# Sheet1.net
KiCad netlist of a schematic drawn in Altium Designer
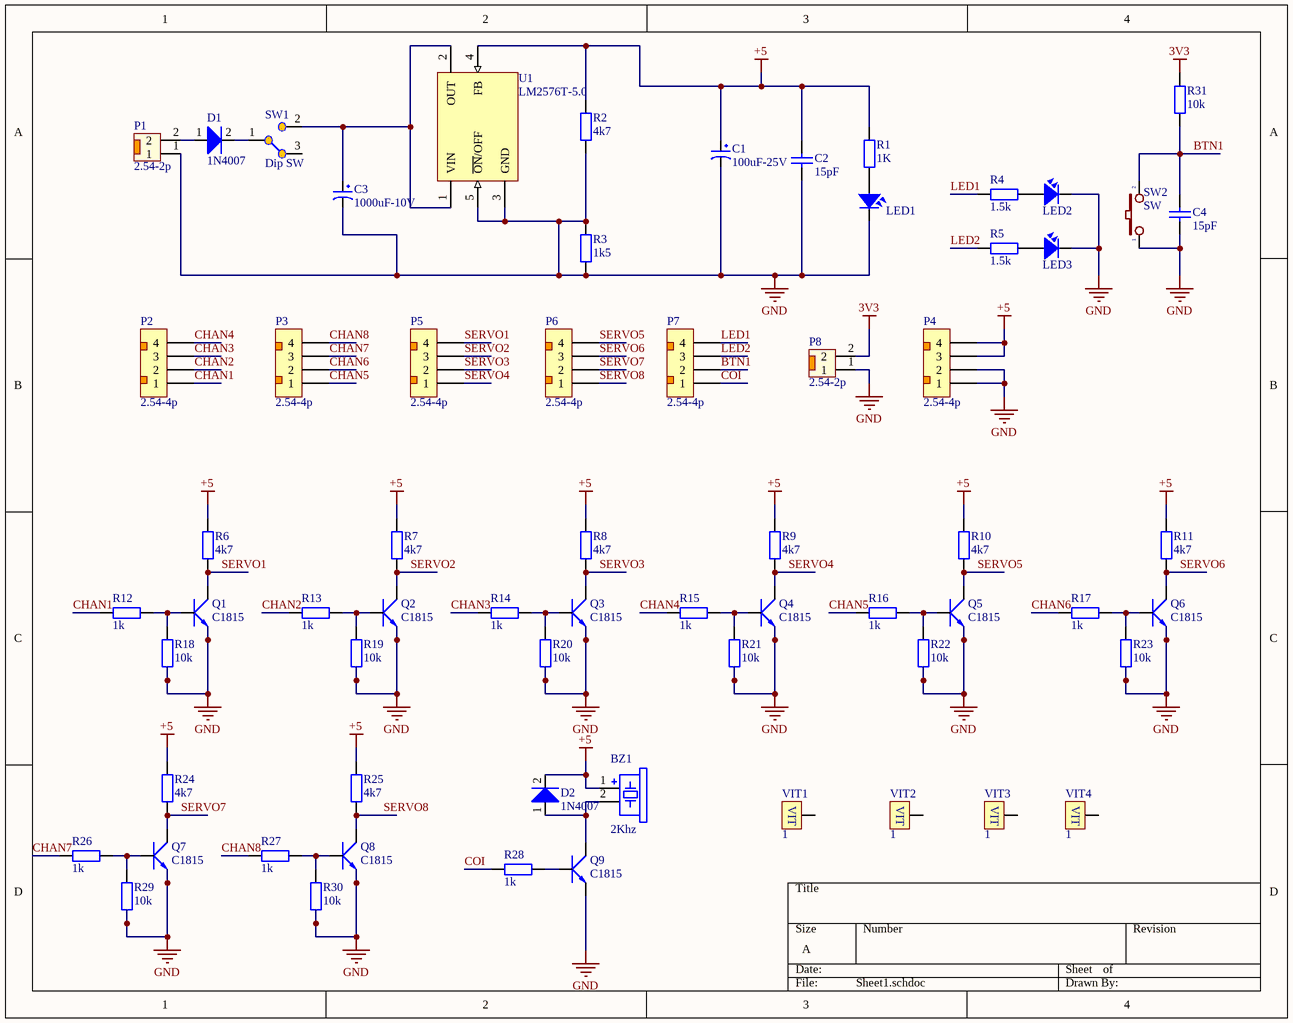
[diagram p0: Sheet1.schdoc]

(export (version "E")
  (design (tool "Eeschema 10.0.6"))
  (components
    (comp (ref "BZ1")
      (value "2Khz")
      (footprint "coi xung")
      (description "Cắm")
      (libsource (lib "NhomLib (1)") (part "Coi xung 2Khz"))
    )
    (comp (ref "C1")
      (value "100uF-25V")
      (footprint "tu hoa 5mm")
      (description "Cắm")
      (libsource (lib "NhomLib (1)") (part "Tu Hoa 100uF 25V 6x11"))
    )
    (comp (ref "C2")
      (value "15pF")
      (footprint "tu gom")
      (description "Cắm")
      (libsource (lib "NhomLib (1)") (part "Tu gom 15pF 50V"))
    )
    (comp (ref "C3")
      (value "1000uF-10V")
      (footprint "tu hoa 10mm")
      (description "Cắm")
      (libsource (lib "NhomLib (1)") (part "Tu Hoa 1000uF 10V 10x12"))
    )
    (comp (ref "C4")
      (value "15pF")
      (footprint "tu gom")
      (description "Cắm")
      (libsource (lib "NhomLib (1)") (part "Tu gom 15pF 50V"))
    )
    (comp (ref "D1")
      (value "1N4007")
      (footprint "1N4007")
      (description "Diode LS 1A 1000V DO-41")
      (libsource (lib "NhomLib (1)") (part "1N4007"))
    )
    (comp (ref "D2")
      (value "1N4007")
      (footprint "1N4007")
      (description "Diode LS 1A 1000V DO-41")
      (libsource (lib "NhomLib (1)") (part "1N4007"))
    )
    (comp (ref "LED1")
      (value "LED")
      (footprint "LED-3")
      (description "LED Single colour Green and Red")
      (libsource (lib "NhomLib (1)") (part "LED"))
    )
    (comp (ref "LED2")
      (value "LED")
      (footprint "LED-3")
      (description "LED Single colour Green and Red")
      (libsource (lib "NhomLib (1)") (part "LED"))
    )
    (comp (ref "LED3")
      (value "LED")
      (footprint "LED-3")
      (description "LED Single colour Green and Red")
      (libsource (lib "NhomLib (1)") (part "LED"))
    )
    (comp (ref "P1")
      (value "2.54-2p")
      (footprint "Header Duc Thang 2P 2.54")
      (description "Cắm")
      (libsource (lib "NhomLib (1)") (part "Header 2.54-2p Duc Thang"))
    )
    (comp (ref "P2")
      (value "2.54-4p")
      (footprint "Header Duc Thang 4p 2.54")
      (description "Cắm")
      (libsource (lib "NhomLib (1)") (part "Header 2.54_4p Duc Thang"))
    )
    (comp (ref "P3")
      (value "2.54-4p")
      (footprint "Header Duc Thang 4p 2.54")
      (description "Cắm")
      (libsource (lib "NhomLib (1)") (part "Header 2.54_4p Duc Thang"))
    )
    (comp (ref "P4")
      (value "2.54-4p")
      (footprint "Header Duc Thang 4p 2.54")
      (description "Cắm")
      (libsource (lib "NhomLib (1)") (part "Header 2.54_4p Duc Thang"))
    )
    (comp (ref "P5")
      (value "2.54-4p")
      (footprint "Header Duc Thang 4p 2.54")
      (description "Cắm")
      (libsource (lib "NhomLib (1)") (part "Header 2.54_4p Duc Thang"))
    )
    (comp (ref "P6")
      (value "2.54-4p")
      (footprint "Header Duc Thang 4p 2.54")
      (description "Cắm")
      (libsource (lib "NhomLib (1)") (part "Header 2.54_4p Duc Thang"))
    )
    (comp (ref "P7")
      (value "2.54-4p")
      (footprint "Header Duc Thang 4p 2.54")
      (description "Cắm")
      (libsource (lib "NhomLib (1)") (part "Header 2.54_4p Duc Thang"))
    )
    (comp (ref "P8")
      (value "2.54-2p")
      (footprint "Header Duc Thang 2P 2.54")
      (description "Cắm")
      (libsource (lib "NhomLib (1)") (part "Header 2.54-2p Duc Thang"))
    )
    (comp (ref "Q1")
      (value "C1815")
      (footprint "QTO-92")
      (description "NPN 600mW, ECB")
      (libsource (lib "syhaunguyen") (part "C1815"))
    )
    (comp (ref "Q2")
      (value "C1815")
      (footprint "QTO-92")
      (description "NPN 600mW, ECB")
      (libsource (lib "syhaunguyen") (part "C1815"))
    )
    (comp (ref "Q3")
      (value "C1815")
      (footprint "QTO-92")
      (description "NPN 600mW, ECB")
      (libsource (lib "syhaunguyen") (part "C1815"))
    )
    (comp (ref "Q4")
      (value "C1815")
      (footprint "QTO-92")
      (description "NPN 600mW, ECB")
      (libsource (lib "syhaunguyen") (part "C1815"))
    )
    (comp (ref "Q5")
      (value "C1815")
      (footprint "QTO-92")
      (description "NPN 600mW, ECB")
      (libsource (lib "syhaunguyen") (part "C1815"))
    )
    (comp (ref "Q6")
      (value "C1815")
      (footprint "QTO-92")
      (description "NPN 600mW, ECB")
      (libsource (lib "syhaunguyen") (part "C1815"))
    )
    (comp (ref "Q7")
      (value "C1815")
      (footprint "QTO-92")
      (description "NPN 600mW, ECB")
      (libsource (lib "syhaunguyen") (part "C1815"))
    )
    (comp (ref "Q8")
      (value "C1815")
      (footprint "QTO-92")
      (description "NPN 600mW, ECB")
      (libsource (lib "syhaunguyen") (part "C1815"))
    )
    (comp (ref "Q9")
      (value "C1815")
      (footprint "QTO-92")
      (description "NPN 600mW, ECB")
      (libsource (lib "syhaunguyen") (part "C1815"))
    )
    (comp (ref "R1")
      (value "1K")
      (footprint "tro vach 1/4w")
      (description "Cắm")
      (libsource (lib "NhomLib (1)") (part "Tro Vach 1/4W 5% 1.5k"))
    )
    (comp (ref "R2")
      (value "4k7")
      (footprint "tro vach 1/4w")
      (description "Cắm")
      (libsource (lib "NhomLib (1)") (part "Tro Vach 1/4W 5% 1.5k"))
    )
    (comp (ref "R3")
      (value "1k5")
      (footprint "tro vach 1/4w")
      (description "Cắm")
      (libsource (lib "NhomLib (1)") (part "Tro Vach 1/4W 5% 1.5k"))
    )
    (comp (ref "R4")
      (value "1.5k")
      (footprint "tro vach 1/4w")
      (description "Cắm")
      (libsource (lib "NhomLib (1)") (part "Tro Vach 1/4W 5% 1.5k"))
    )
    (comp (ref "R5")
      (value "1.5k")
      (footprint "tro vach 1/4w")
      (description "Cắm")
      (libsource (lib "NhomLib (1)") (part "Tro Vach 1/4W 5% 1.5k"))
    )
    (comp (ref "R6")
      (value "4k7")
      (footprint "tro vach 1/4w")
      (description "Cắm")
      (libsource (lib "NhomLib (1)") (part "Tro Vach 1/4W 5% 1.5k"))
    )
    (comp (ref "R7")
      (value "4k7")
      (footprint "tro vach 1/4w")
      (description "Cắm")
      (libsource (lib "NhomLib (1)") (part "Tro Vach 1/4W 5% 1.5k"))
    )
    (comp (ref "R8")
      (value "4k7")
      (footprint "tro vach 1/4w")
      (description "Cắm")
      (libsource (lib "NhomLib (1)") (part "Tro Vach 1/4W 5% 1.5k"))
    )
    (comp (ref "R9")
      (value "4k7")
      (footprint "tro vach 1/4w")
      (description "Cắm")
      (libsource (lib "NhomLib (1)") (part "Tro Vach 1/4W 5% 1.5k"))
    )
    (comp (ref "R10")
      (value "4k7")
      (footprint "tro vach 1/4w")
      (description "Cắm")
      (libsource (lib "NhomLib (1)") (part "Tro Vach 1/4W 5% 1.5k"))
    )
    (comp (ref "R11")
      (value "4k7")
      (footprint "tro vach 1/4w")
      (description "Cắm")
      (libsource (lib "NhomLib (1)") (part "Tro Vach 1/4W 5% 1.5k"))
    )
    (comp (ref "R12")
      (value "1k")
      (footprint "tro vach 1/4w")
      (description "Cắm")
      (libsource (lib "NhomLib (1)") (part "Tro Vach 1/4W 5% 1.5k"))
    )
    (comp (ref "R13")
      (value "1k")
      (footprint "tro vach 1/4w")
      (description "Cắm")
      (libsource (lib "NhomLib (1)") (part "Tro Vach 1/4W 5% 1.5k"))
    )
    (comp (ref "R14")
      (value "1k")
      (footprint "tro vach 1/4w")
      (description "Cắm")
      (libsource (lib "NhomLib (1)") (part "Tro Vach 1/4W 5% 1.5k"))
    )
    (comp (ref "R15")
      (value "1k")
      (footprint "tro vach 1/4w")
      (description "Cắm")
      (libsource (lib "NhomLib (1)") (part "Tro Vach 1/4W 5% 1.5k"))
    )
    (comp (ref "R16")
      (value "1k")
      (footprint "tro vach 1/4w")
      (description "Cắm")
      (libsource (lib "NhomLib (1)") (part "Tro Vach 1/4W 5% 1.5k"))
    )
    (comp (ref "R17")
      (value "1k")
      (footprint "tro vach 1/4w")
      (description "Cắm")
      (libsource (lib "NhomLib (1)") (part "Tro Vach 1/4W 5% 1.5k"))
    )
    (comp (ref "R18")
      (value "10k")
      (footprint "tro vach 1/4w")
      (description "Cắm")
      (libsource (lib "NhomLib (1)") (part "Tro Vach 1/4W 5% 1.5k"))
    )
    (comp (ref "R19")
      (value "10k")
      (footprint "tro vach 1/4w")
      (description "Cắm")
      (libsource (lib "NhomLib (1)") (part "Tro Vach 1/4W 5% 1.5k"))
    )
    (comp (ref "R20")
      (value "10k")
      (footprint "tro vach 1/4w")
      (description "Cắm")
      (libsource (lib "NhomLib (1)") (part "Tro Vach 1/4W 5% 1.5k"))
    )
    (comp (ref "R21")
      (value "10k")
      (footprint "tro vach 1/4w")
      (description "Cắm")
      (libsource (lib "NhomLib (1)") (part "Tro Vach 1/4W 5% 1.5k"))
    )
    (comp (ref "R22")
      (value "10k")
      (footprint "tro vach 1/4w")
      (description "Cắm")
      (libsource (lib "NhomLib (1)") (part "Tro Vach 1/4W 5% 1.5k"))
    )
    (comp (ref "R23")
      (value "10k")
      (footprint "tro vach 1/4w")
      (description "Cắm")
      (libsource (lib "NhomLib (1)") (part "Tro Vach 1/4W 5% 1.5k"))
    )
    (comp (ref "R24")
      (value "4k7")
      (footprint "tro vach 1/4w")
      (description "Cắm")
      (libsource (lib "NhomLib (1)") (part "Tro Vach 1/4W 5% 1.5k"))
    )
    (comp (ref "R25")
      (value "4k7")
      (footprint "tro vach 1/4w")
      (description "Cắm")
      (libsource (lib "NhomLib (1)") (part "Tro Vach 1/4W 5% 1.5k"))
    )
    (comp (ref "R26")
      (value "1k")
      (footprint "tro vach 1/4w")
      (description "Cắm")
      (libsource (lib "NhomLib (1)") (part "Tro Vach 1/4W 5% 1.5k"))
    )
    (comp (ref "R27")
      (value "1k")
      (footprint "tro vach 1/4w")
      (description "Cắm")
      (libsource (lib "NhomLib (1)") (part "Tro Vach 1/4W 5% 1.5k"))
    )
    (comp (ref "R28")
      (value "1k")
      (footprint "tro vach 1/4w")
      (description "Cắm")
      (libsource (lib "NhomLib (1)") (part "Tro Vach 1/4W 5% 1.5k"))
    )
    (comp (ref "R29")
      (value "10k")
      (footprint "tro vach 1/4w")
      (description "Cắm")
      (libsource (lib "NhomLib (1)") (part "Tro Vach 1/4W 5% 1.5k"))
    )
    (comp (ref "R30")
      (value "10k")
      (footprint "tro vach 1/4w")
      (description "Cắm")
      (libsource (lib "NhomLib (1)") (part "Tro Vach 1/4W 5% 1.5k"))
    )
    (comp (ref "R31")
      (value "10k")
      (footprint "tro vach 1/4w")
      (description "Cắm")
      (libsource (lib "NhomLib (1)") (part "Tro Vach 1/4W 5% 1.5k"))
    )
    (comp (ref "SW1")
      (value "Dip SW")
      (footprint "SW3P")
      (description "Dip Switch 3 pin")
      (libsource (lib "VPMyLibrary") (part "Switch3P"))
    )
    (comp (ref "SW2")
      (value "SW")
      (footprint "SW2")
      (description "Switch button 2 pin")
      (libsource (lib "syhaunguyen") (part "SW2"))
    )
    (comp (ref "U1")
      (value "LM2576T-5.0")
      (footprint "LM2576t")
      (description "SIMPLE SWITCHER; 3A Step-Down Voltage Regulator")
      (fields
        (field (name "MANUFACTURER") "National Semiconductor")
        (field (name "DIGIKEYPARTNUMBER") "LM2576T-5.0-ND")
        (field (name "PUBLISHER") "Altium Limited")
      )
      (libsource (lib "NBBLib 14-03-2012") (part "LM2576T-5.0"))
    )
    (comp (ref "VIT1")
      (value "1")
      (footprint "VIT")
      (description "Oc Vit")
      (libsource (lib "NhomLib (1)") (part "VIT"))
    )
    (comp (ref "VIT2")
      (value "1")
      (footprint "VIT")
      (description "Oc Vit")
      (libsource (lib "NhomLib (1)") (part "VIT"))
    )
    (comp (ref "VIT3")
      (value "1")
      (footprint "VIT")
      (description "Oc Vit")
      (libsource (lib "NhomLib (1)") (part "VIT"))
    )
    (comp (ref "VIT4")
      (value "1")
      (footprint "VIT")
      (description "Oc Vit")
      (libsource (lib "NhomLib (1)") (part "VIT"))
    )
  )
  (nets
    (net (code "1") (name "+5") (class "Default")
      (node (ref "BZ1") (pin "1") (pinfunction "1_1") (pintype "passive"))
      (node (ref "C1") (pin "1") (pinfunction "1_1") (pintype "passive"))
      (node (ref "C2") (pin "1") (pinfunction "1_1") (pintype "passive"))
      (node (ref "D2") (pin "2") (pinfunction "K_2") (pintype "passive"))
      (node (ref "P4") (pin "3") (pinfunction "3_3") (pintype "passive"))
      (node (ref "P4") (pin "4") (pinfunction "4_4") (pintype "passive"))
      (node (ref "R1") (pin "2") (pinfunction "2_2") (pintype "passive"))
      (node (ref "R10") (pin "2") (pinfunction "2_2") (pintype "passive"))
      (node (ref "R11") (pin "2") (pinfunction "2_2") (pintype "passive"))
      (node (ref "R2") (pin "2") (pinfunction "2_2") (pintype "passive"))
      (node (ref "R24") (pin "2") (pinfunction "2_2") (pintype "passive"))
      (node (ref "R25") (pin "2") (pinfunction "2_2") (pintype "passive"))
      (node (ref "R6") (pin "2") (pinfunction "2_2") (pintype "passive"))
      (node (ref "R7") (pin "2") (pinfunction "2_2") (pintype "passive"))
      (node (ref "R8") (pin "2") (pinfunction "2_2") (pintype "passive"))
      (node (ref "R9") (pin "2") (pinfunction "2_2") (pintype "passive"))
      (node (ref "U1") (pin "4") (pinfunction "FB_4") (pintype "input"))
    )
    (net (code "2") (name "/BTN1") (class "Default")
      (node (ref "C4") (pin "1") (pinfunction "1_1") (pintype "passive"))
      (node (ref "P7") (pin "2") (pinfunction "2_2") (pintype "passive"))
      (node (ref "R31") (pin "1") (pinfunction "1_1") (pintype "passive"))
      (node (ref "SW2") (pin "2") (pinfunction "2_2") (pintype "passive"))
    )
    (net (code "3") (name "/CHAN1") (class "Default")
      (node (ref "P2") (pin "1") (pinfunction "1_1") (pintype "passive"))
      (node (ref "R12") (pin "1") (pinfunction "1_1") (pintype "passive"))
    )
    (net (code "4") (name "/CHAN2") (class "Default")
      (node (ref "P2") (pin "2") (pinfunction "2_2") (pintype "passive"))
      (node (ref "R13") (pin "1") (pinfunction "1_1") (pintype "passive"))
    )
    (net (code "5") (name "/CHAN3") (class "Default")
      (node (ref "P2") (pin "3") (pinfunction "3_3") (pintype "passive"))
      (node (ref "R14") (pin "1") (pinfunction "1_1") (pintype "passive"))
    )
    (net (code "6") (name "/CHAN4") (class "Default")
      (node (ref "P2") (pin "4") (pinfunction "4_4") (pintype "passive"))
      (node (ref "R15") (pin "1") (pinfunction "1_1") (pintype "passive"))
    )
    (net (code "7") (name "/CHAN5") (class "Default")
      (node (ref "P3") (pin "1") (pinfunction "1_1") (pintype "passive"))
      (node (ref "R16") (pin "1") (pinfunction "1_1") (pintype "passive"))
    )
    (net (code "8") (name "/CHAN6") (class "Default")
      (node (ref "P3") (pin "2") (pinfunction "2_2") (pintype "passive"))
      (node (ref "R17") (pin "1") (pinfunction "1_1") (pintype "passive"))
    )
    (net (code "9") (name "/CHAN7") (class "Default")
      (node (ref "P3") (pin "3") (pinfunction "3_3") (pintype "passive"))
      (node (ref "R26") (pin "1") (pinfunction "1_1") (pintype "passive"))
    )
    (net (code "10") (name "/CHAN8") (class "Default")
      (node (ref "P3") (pin "4") (pinfunction "4_4") (pintype "passive"))
      (node (ref "R27") (pin "1") (pinfunction "1_1") (pintype "passive"))
    )
    (net (code "11") (name "/COI") (class "Default")
      (node (ref "P7") (pin "1") (pinfunction "1_1") (pintype "passive"))
      (node (ref "R28") (pin "1") (pinfunction "1_1") (pintype "passive"))
    )
    (net (code "12") (name "/LED1") (class "Default")
      (node (ref "P7") (pin "4") (pinfunction "4_4") (pintype "passive"))
      (node (ref "R4") (pin "2") (pinfunction "2_2") (pintype "passive"))
    )
    (net (code "13") (name "/LED2") (class "Default")
      (node (ref "P7") (pin "3") (pinfunction "3_3") (pintype "passive"))
      (node (ref "R5") (pin "2") (pinfunction "2_2") (pintype "passive"))
    )
    (net (code "14") (name "/SERVO1") (class "Default")
      (node (ref "P5") (pin "4") (pinfunction "4_4") (pintype "passive"))
      (node (ref "Q1") (pin "2") (pinfunction "C_2") (pintype "passive"))
      (node (ref "R6") (pin "1") (pinfunction "1_1") (pintype "passive"))
    )
    (net (code "15") (name "/SERVO2") (class "Default")
      (node (ref "P5") (pin "3") (pinfunction "3_3") (pintype "passive"))
      (node (ref "Q2") (pin "2") (pinfunction "C_2") (pintype "passive"))
      (node (ref "R7") (pin "1") (pinfunction "1_1") (pintype "passive"))
    )
    (net (code "16") (name "/SERVO3") (class "Default")
      (node (ref "P5") (pin "2") (pinfunction "2_2") (pintype "passive"))
      (node (ref "Q3") (pin "2") (pinfunction "C_2") (pintype "passive"))
      (node (ref "R8") (pin "1") (pinfunction "1_1") (pintype "passive"))
    )
    (net (code "17") (name "/SERVO4") (class "Default")
      (node (ref "P5") (pin "1") (pinfunction "1_1") (pintype "passive"))
      (node (ref "Q4") (pin "2") (pinfunction "C_2") (pintype "passive"))
      (node (ref "R9") (pin "1") (pinfunction "1_1") (pintype "passive"))
    )
    (net (code "18") (name "/SERVO5") (class "Default")
      (node (ref "P6") (pin "4") (pinfunction "4_4") (pintype "passive"))
      (node (ref "Q5") (pin "2") (pinfunction "C_2") (pintype "passive"))
      (node (ref "R10") (pin "1") (pinfunction "1_1") (pintype "passive"))
    )
    (net (code "19") (name "/SERVO6") (class "Default")
      (node (ref "P6") (pin "3") (pinfunction "3_3") (pintype "passive"))
      (node (ref "Q6") (pin "2") (pinfunction "C_2") (pintype "passive"))
      (node (ref "R11") (pin "1") (pinfunction "1_1") (pintype "passive"))
    )
    (net (code "20") (name "/SERVO7") (class "Default")
      (node (ref "P6") (pin "2") (pinfunction "2_2") (pintype "passive"))
      (node (ref "Q7") (pin "2") (pinfunction "C_2") (pintype "passive"))
      (node (ref "R24") (pin "1") (pinfunction "1_1") (pintype "passive"))
    )
    (net (code "21") (name "/SERVO8") (class "Default")
      (node (ref "P6") (pin "1") (pinfunction "1_1") (pintype "passive"))
      (node (ref "Q8") (pin "2") (pinfunction "C_2") (pintype "passive"))
      (node (ref "R25") (pin "1") (pinfunction "1_1") (pintype "passive"))
    )
    (net (code "22") (name "3V3") (class "Default")
      (node (ref "P8") (pin "2") (pinfunction "2_2") (pintype "passive"))
      (node (ref "R31") (pin "2") (pinfunction "2_2") (pintype "passive"))
    )
    (net (code "23") (name "GND") (class "Default")
      (node (ref "C1") (pin "2") (pinfunction "2_2") (pintype "passive"))
      (node (ref "C2") (pin "2") (pinfunction "2_2") (pintype "passive"))
      (node (ref "C3") (pin "2") (pinfunction "2_2") (pintype "passive"))
      (node (ref "C4") (pin "2") (pinfunction "2_2") (pintype "passive"))
      (node (ref "LED1") (pin "2") (pinfunction "2_2") (pintype "passive"))
      (node (ref "LED2") (pin "2") (pinfunction "2_2") (pintype "passive"))
      (node (ref "LED3") (pin "2") (pinfunction "2_2") (pintype "passive"))
      (node (ref "P1") (pin "1") (pinfunction "1_1") (pintype "passive"))
      (node (ref "P4") (pin "1") (pinfunction "1_1") (pintype "passive"))
      (node (ref "P4") (pin "2") (pinfunction "2_2") (pintype "passive"))
      (node (ref "P8") (pin "1") (pinfunction "1_1") (pintype "passive"))
      (node (ref "Q1") (pin "1") (pinfunction "E_1") (pintype "passive"))
      (node (ref "Q2") (pin "1") (pinfunction "E_1") (pintype "passive"))
      (node (ref "Q3") (pin "1") (pinfunction "E_1") (pintype "passive"))
      (node (ref "Q4") (pin "1") (pinfunction "E_1") (pintype "passive"))
      (node (ref "Q5") (pin "1") (pinfunction "E_1") (pintype "passive"))
      (node (ref "Q6") (pin "1") (pinfunction "E_1") (pintype "passive"))
      (node (ref "Q7") (pin "1") (pinfunction "E_1") (pintype "passive"))
      (node (ref "Q8") (pin "1") (pinfunction "E_1") (pintype "passive"))
      (node (ref "Q9") (pin "1") (pinfunction "E_1") (pintype "passive"))
      (node (ref "R18") (pin "1") (pinfunction "1_1") (pintype "passive"))
      (node (ref "R19") (pin "1") (pinfunction "1_1") (pintype "passive"))
      (node (ref "R2") (pin "1") (pinfunction "1_1") (pintype "passive"))
      (node (ref "R20") (pin "1") (pinfunction "1_1") (pintype "passive"))
      (node (ref "R21") (pin "1") (pinfunction "1_1") (pintype "passive"))
      (node (ref "R22") (pin "1") (pinfunction "1_1") (pintype "passive"))
      (node (ref "R23") (pin "1") (pinfunction "1_1") (pintype "passive"))
      (node (ref "R29") (pin "1") (pinfunction "1_1") (pintype "passive"))
      (node (ref "R3") (pin "1") (pinfunction "1_1") (pintype "passive"))
      (node (ref "R3") (pin "2") (pinfunction "2_2") (pintype "passive"))
      (node (ref "R30") (pin "1") (pinfunction "1_1") (pintype "passive"))
      (node (ref "SW2") (pin "1") (pinfunction "1_1") (pintype "passive"))
      (node (ref "U1") (pin "3") (pinfunction "GND_3") (pintype "power_in"))
      (node (ref "U1") (pin "5") (pinfunction "~{ON}/OFF_5") (pintype "input"))
    )
    (net (code "24") (name "Net-(D1-A)") (class "Default")
      (node (ref "D1") (pin "1") (pinfunction "A_1") (pintype "passive"))
      (node (ref "P1") (pin "2") (pinfunction "2_2") (pintype "passive"))
    )
    (net (code "25") (name "Net-(D1-K)") (class "Default")
      (node (ref "D1") (pin "2") (pinfunction "K_2") (pintype "passive"))
      (node (ref "SW1") (pin "1") (pinfunction "COM_1") (pintype "passive"))
    )
    (net (code "26") (name "Net-(D2-A)") (class "Default")
      (node (ref "BZ1") (pin "2") (pinfunction "2_2") (pintype "passive"))
      (node (ref "D2") (pin "1") (pinfunction "A_1") (pintype "passive"))
      (node (ref "Q9") (pin "2") (pinfunction "C_2") (pintype "passive"))
    )
    (net (code "27") (name "Net-(LED1-Pad1)") (class "Default")
      (node (ref "LED1") (pin "1") (pinfunction "1_1") (pintype "passive"))
      (node (ref "R1") (pin "1") (pinfunction "1_1") (pintype "passive"))
    )
    (net (code "28") (name "Net-(LED2-Pad1)") (class "Default")
      (node (ref "LED2") (pin "1") (pinfunction "1_1") (pintype "passive"))
      (node (ref "R4") (pin "1") (pinfunction "1_1") (pintype "passive"))
    )
    (net (code "29") (name "Net-(LED3-Pad1)") (class "Default")
      (node (ref "LED3") (pin "1") (pinfunction "1_1") (pintype "passive"))
      (node (ref "R5") (pin "1") (pinfunction "1_1") (pintype "passive"))
    )
    (net (code "30") (name "Net-(Q1-B)") (class "Default")
      (node (ref "Q1") (pin "3") (pinfunction "B_3") (pintype "passive"))
      (node (ref "R12") (pin "2") (pinfunction "2_2") (pintype "passive"))
      (node (ref "R18") (pin "2") (pinfunction "2_2") (pintype "passive"))
    )
    (net (code "31") (name "Net-(Q2-B)") (class "Default")
      (node (ref "Q2") (pin "3") (pinfunction "B_3") (pintype "passive"))
      (node (ref "R13") (pin "2") (pinfunction "2_2") (pintype "passive"))
      (node (ref "R19") (pin "2") (pinfunction "2_2") (pintype "passive"))
    )
    (net (code "32") (name "Net-(Q3-B)") (class "Default")
      (node (ref "Q3") (pin "3") (pinfunction "B_3") (pintype "passive"))
      (node (ref "R14") (pin "2") (pinfunction "2_2") (pintype "passive"))
      (node (ref "R20") (pin "2") (pinfunction "2_2") (pintype "passive"))
    )
    (net (code "33") (name "Net-(Q4-B)") (class "Default")
      (node (ref "Q4") (pin "3") (pinfunction "B_3") (pintype "passive"))
      (node (ref "R15") (pin "2") (pinfunction "2_2") (pintype "passive"))
      (node (ref "R21") (pin "2") (pinfunction "2_2") (pintype "passive"))
    )
    (net (code "34") (name "Net-(Q5-B)") (class "Default")
      (node (ref "Q5") (pin "3") (pinfunction "B_3") (pintype "passive"))
      (node (ref "R16") (pin "2") (pinfunction "2_2") (pintype "passive"))
      (node (ref "R22") (pin "2") (pinfunction "2_2") (pintype "passive"))
    )
    (net (code "35") (name "Net-(Q6-B)") (class "Default")
      (node (ref "Q6") (pin "3") (pinfunction "B_3") (pintype "passive"))
      (node (ref "R17") (pin "2") (pinfunction "2_2") (pintype "passive"))
      (node (ref "R23") (pin "2") (pinfunction "2_2") (pintype "passive"))
    )
    (net (code "36") (name "Net-(Q7-B)") (class "Default")
      (node (ref "Q7") (pin "3") (pinfunction "B_3") (pintype "passive"))
      (node (ref "R26") (pin "2") (pinfunction "2_2") (pintype "passive"))
      (node (ref "R29") (pin "2") (pinfunction "2_2") (pintype "passive"))
    )
    (net (code "37") (name "Net-(Q8-B)") (class "Default")
      (node (ref "Q8") (pin "3") (pinfunction "B_3") (pintype "passive"))
      (node (ref "R27") (pin "2") (pinfunction "2_2") (pintype "passive"))
      (node (ref "R30") (pin "2") (pinfunction "2_2") (pintype "passive"))
    )
    (net (code "38") (name "Net-(Q9-B)") (class "Default")
      (node (ref "Q9") (pin "3") (pinfunction "B_3") (pintype "passive"))
      (node (ref "R28") (pin "2") (pinfunction "2_2") (pintype "passive"))
    )
    (net (code "39") (name "Net-(SW1-NC)") (class "Default")
      (node (ref "C3") (pin "1") (pinfunction "1_1") (pintype "passive"))
      (node (ref "SW1") (pin "2") (pinfunction "NC_2") (pintype "passive"))
      (node (ref "U1") (pin "1") (pinfunction "VIN_1") (pintype "power_in"))
      (node (ref "U1") (pin "2") (pinfunction "OUT_2") (pintype "power_in"))
    )
    (net (code "40") (name "unconnected-(SW1-NO-Pad3)") (class "Default")
      (node (ref "SW1") (pin "3") (pinfunction "NO_3") (pintype "passive"))
    )
    (net (code "41") (name "unconnected-(VIT1-1-PadVIT1)") (class "Default")
      (node (ref "VIT1") (pin "VIT1") (pinfunction "1_VIT1") (pintype "passive"))
    )
    (net (code "42") (name "unconnected-(VIT2-1-PadVIT1)") (class "Default")
      (node (ref "VIT2") (pin "VIT1") (pinfunction "1_VIT1") (pintype "passive"))
    )
    (net (code "43") (name "unconnected-(VIT3-1-PadVIT1)") (class "Default")
      (node (ref "VIT3") (pin "VIT1") (pinfunction "1_VIT1") (pintype "passive"))
    )
    (net (code "44") (name "unconnected-(VIT4-1-PadVIT1)") (class "Default")
      (node (ref "VIT4") (pin "VIT1") (pinfunction "1_VIT1") (pintype "passive"))
    )
  )
)
